# ProPrj_EPICS_Project_PCBs_2024-10-20.net
KiCad netlist of a schematic drawn in EasyEDA Pro
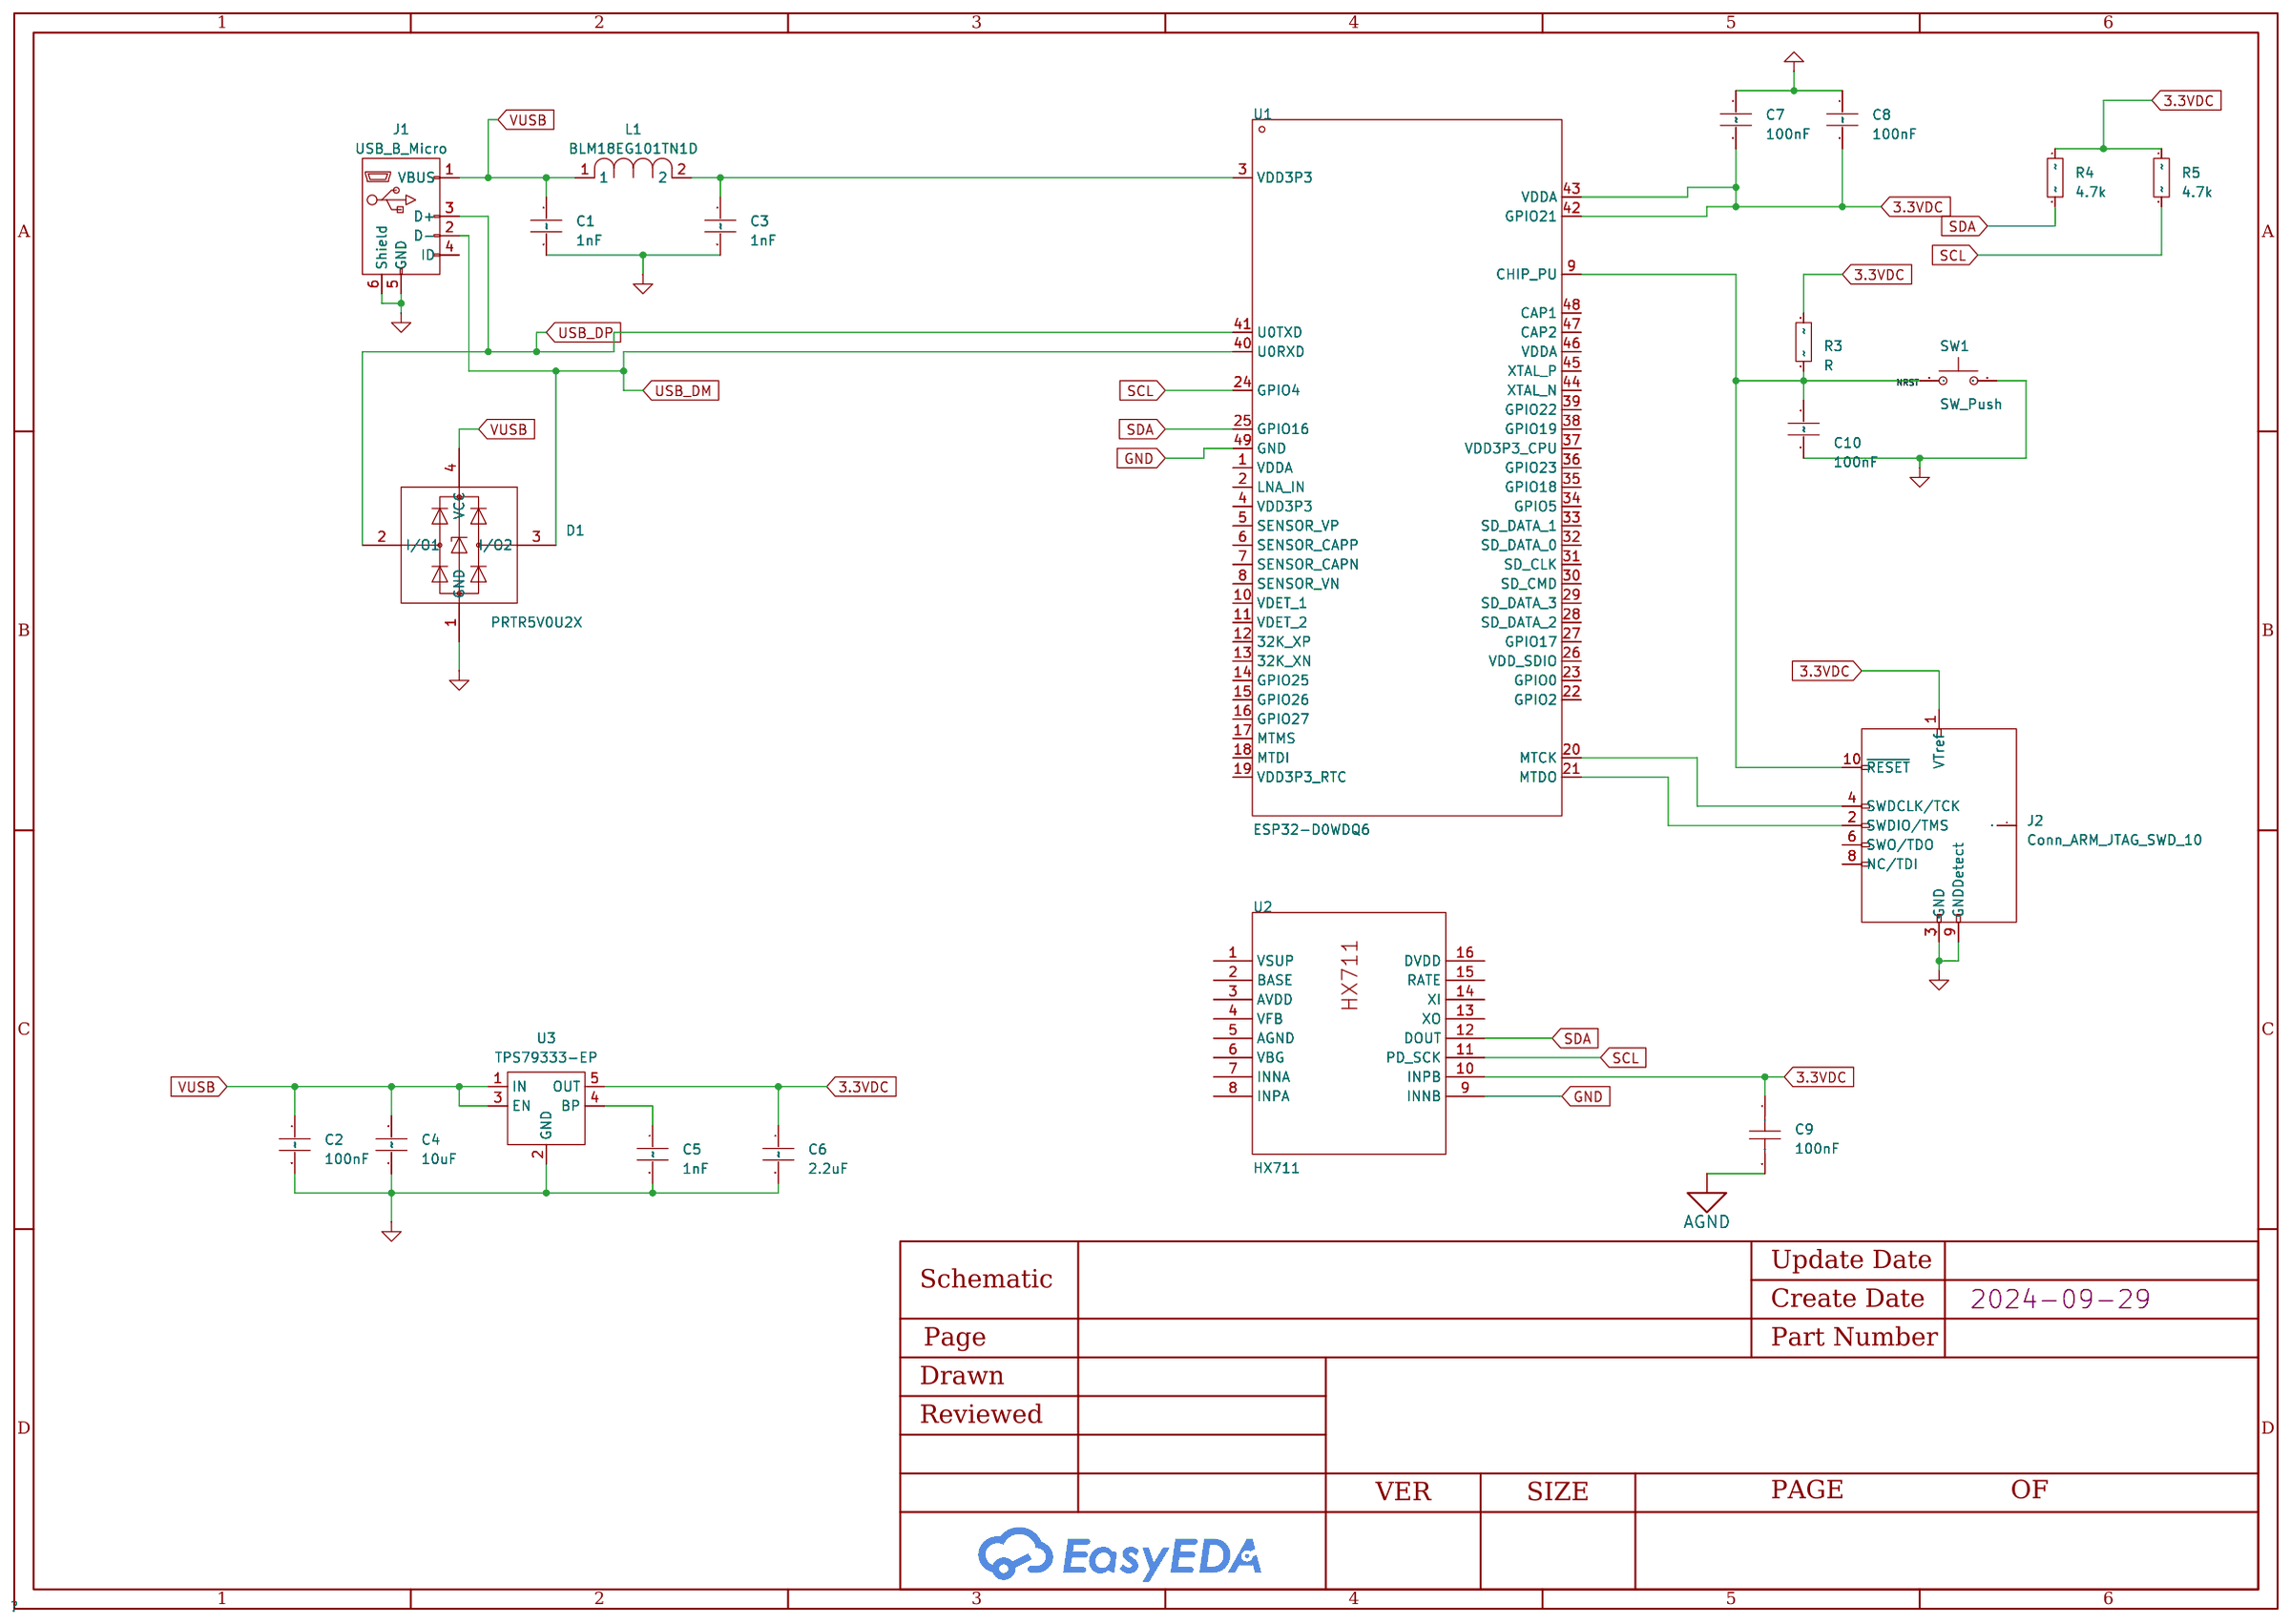
[diagram p0: schematic sheet]

(export (version "E")
  (design (tool "Eeschema 10.0.6"))
  (components
    (comp (ref "C1") (value "1nF") (libsource (lib "easyedapro") (part "Device_C")))
    (comp (ref "C2") (value "100nF") (libsource (lib "easyedapro") (part "Device_C")))
    (comp (ref "C3") (value "1nF") (libsource (lib "easyedapro") (part "Device_C")))
    (comp (ref "C4") (value "10uF") (libsource (lib "easyedapro") (part "Device_C")))
    (comp (ref "C5") (value "1nF") (libsource (lib "easyedapro") (part "Device_C")))
    (comp (ref "C6") (value "2.2uF") (libsource (lib "easyedapro") (part "Device_C")))
    (comp (ref "C7") (value "100nF") (libsource (lib "easyedapro") (part "Device_C")))
    (comp (ref "C8") (value "100nF") (libsource (lib "easyedapro") (part "Device_C")))
    (comp (ref "C9")
      (value "100nF")
      (footprint "easyedapro:C0603")
      (libsource (lib "easyedapro") (part "CAP"))
    )
    (comp (ref "C10") (value "100nF") (libsource (lib "easyedapro") (part "Device_C")))
    (comp (ref "D1") (value "PRTR5V0U2X") (libsource (lib "easyedapro") (part "Power_Protection_PRTR5V0U2X")))
    (comp (ref "J1") (value "USB_B_Micro") (libsource (lib "easyedapro") (part "Connector_USB_B_Micro")))
    (comp (ref "J2")
      (value "Conn_ARM_JTAG_SWD_10")
      (libsource (lib "easyedapro") (part "Connector_Conn_ARM_JTAG_SWD_10"))
    )
    (comp (ref "L1")
      (value "BLM18EG101TN1D")
      (libsource (lib "easyedapro") (part "COURSE_COMPONENTS_BLM18EG101TN1D"))
    )
    (comp (ref "R3") (value "R") (libsource (lib "easyedapro") (part "Device_R")))
    (comp (ref "R4") (value "4.7k") (libsource (lib "easyedapro") (part "Device_R")))
    (comp (ref "R5") (value "4.7k") (libsource (lib "easyedapro") (part "Device_R")))
    (comp (ref "SW1") (value "SW_Push") (libsource (lib "easyedapro") (part "Switch_SW_Push")))
    (comp (ref "U1")
      (value "ESP32-D0WDQ6")
      (footprint "easyedapro:QFN-48_L6.0-W6.0-P0.40-BL-EP3.8")
      (fields (field (name "Manufacturer") "ESPRESSIF(乐鑫)"))
      (libsource (lib "easyedapro") (part "ESP32-D0WDQ6"))
    )
    (comp (ref "U2")
      (value "HX711")
      (footprint "easyedapro:SOP-16_L10.0-W3.9-P1.27-LS6.0-BL")
      (fields (field (name "Manufacturer") "AVIA(海芯科技)"))
      (libsource (lib "easyedapro") (part "HX711"))
    )
    (comp (ref "U3")
      (value "TPS79333-EP")
      (libsource (lib "easyedapro") (part "Regulator_Linear_TPS79333-EP"))
    )
  )
  (nets
    (net (code "1") (name "/NRST") (class "Default")
      (node (ref "C10") (pin "2") (pinfunction "~_2") (pintype "unspecified"))
      (node (ref "J2") (pin "10") (pinfunction "~{RESET}_10") (pintype "unspecified"))
      (node (ref "R3") (pin "2") (pinfunction "~_2") (pintype "unspecified"))
      (node (ref "SW1") (pin "1") (pinfunction "1_1") (pintype "unspecified"))
      (node (ref "U1") (pin "9") (pinfunction "CHIP_PU_9") (pintype "input"))
    )
    (net (code "2") (name "3.3VDC") (class "Default")
      (node (ref "C6") (pin "1") (pinfunction "~_1") (pintype "unspecified"))
      (node (ref "C7") (pin "1") (pinfunction "~_1") (pintype "unspecified"))
      (node (ref "C8") (pin "1") (pinfunction "~_1") (pintype "unspecified"))
      (node (ref "C9") (pin "1") (pinfunction "1_1") (pintype "input"))
      (node (ref "J2") (pin "1") (pinfunction "VTref_1") (pintype "unspecified"))
      (node (ref "R3") (pin "1") (pinfunction "~_1") (pintype "unspecified"))
      (node (ref "R4") (pin "1") (pinfunction "~_1") (pintype "unspecified"))
      (node (ref "R5") (pin "1") (pinfunction "~_1") (pintype "unspecified"))
      (node (ref "U1") (pin "42") (pinfunction "GPIO21_42") (pintype "input"))
      (node (ref "U1") (pin "43") (pinfunction "VDDA_43") (pintype "input"))
      (node (ref "U2") (pin "10") (pinfunction "INPB_10") (pintype "unspecified"))
      (node (ref "U3") (pin "5") (pinfunction "OUT_5") (pintype "unspecified"))
    )
    (net (code "3") (name "AGND") (class "Default")
      (node (ref "C9") (pin "2") (pinfunction "2_2") (pintype "input"))
    )
    (net (code "4") (name "GND") (class "Default")
      (node (ref "U1") (pin "49") (pinfunction "GND_49") (pintype "input"))
      (node (ref "U2") (pin "9") (pinfunction "INNB_9") (pintype "unspecified"))
    )
    (net (code "5") (name "Net-(C3-~-Pad1)") (class "Default")
      (node (ref "C3") (pin "1") (pinfunction "~_1") (pintype "unspecified"))
      (node (ref "L1") (pin "2") (pinfunction "2_2") (pintype "unspecified"))
      (node (ref "U1") (pin "3") (pinfunction "VDD3P3_3") (pintype "input"))
    )
    (net (code "6") (name "Net-(J2-SWDCLK{slash}TCK)") (class "Default")
      (node (ref "J2") (pin "4") (pinfunction "SWDCLK/TCK_4") (pintype "output"))
      (node (ref "U1") (pin "20") (pinfunction "MTCK_20") (pintype "input"))
    )
    (net (code "7") (name "Net-(J2-SWDIO{slash}TMS)") (class "Default")
      (node (ref "J2") (pin "2") (pinfunction "SWDIO/TMS_2") (pintype "bidirectional"))
      (node (ref "U1") (pin "21") (pinfunction "MTDO_21") (pintype "input"))
    )
    (net (code "8") (name "Net-(U3-BP)") (class "Default")
      (node (ref "C5") (pin "1") (pinfunction "~_1") (pintype "unspecified"))
      (node (ref "U3") (pin "4") (pinfunction "BP_4") (pintype "bidirectional"))
    )
    (net (code "9") (name "POWER_GND") (class "Default")
      (node (ref "C1") (pin "2") (pinfunction "~_2") (pintype "unspecified"))
      (node (ref "C10") (pin "1") (pinfunction "~_1") (pintype "unspecified"))
      (node (ref "C2") (pin "2") (pinfunction "~_2") (pintype "unspecified"))
      (node (ref "C3") (pin "2") (pinfunction "~_2") (pintype "unspecified"))
      (node (ref "C4") (pin "2") (pinfunction "~_2") (pintype "unspecified"))
      (node (ref "C5") (pin "2") (pinfunction "~_2") (pintype "unspecified"))
      (node (ref "C6") (pin "2") (pinfunction "~_2") (pintype "unspecified"))
      (node (ref "C7") (pin "2") (pinfunction "~_2") (pintype "unspecified"))
      (node (ref "C8") (pin "2") (pinfunction "~_2") (pintype "unspecified"))
      (node (ref "D1") (pin "1") (pinfunction "GND_1") (pintype "unspecified"))
      (node (ref "J1") (pin "5") (pinfunction "GND_5") (pintype "unspecified"))
      (node (ref "J1") (pin "6") (pinfunction "Shield_6") (pintype "unspecified"))
      (node (ref "J2") (pin "3") (pinfunction "GND_3") (pintype "unspecified"))
      (node (ref "J2") (pin "5") (pinfunction "GND_5") (pintype "unspecified"))
      (node (ref "J2") (pin "9") (pinfunction "GNDDetect_9") (pintype "unspecified"))
      (node (ref "SW1") (pin "2") (pinfunction "2_2") (pintype "unspecified"))
      (node (ref "U3") (pin "2") (pinfunction "GND_2") (pintype "unspecified"))
    )
    (net (code "10") (name "SCL") (class "Default")
      (node (ref "R5") (pin "2") (pinfunction "~_2") (pintype "unspecified"))
      (node (ref "U1") (pin "24") (pinfunction "GPIO4_24") (pintype "input"))
      (node (ref "U2") (pin "11") (pinfunction "PD_SCK_11") (pintype "unspecified"))
    )
    (net (code "11") (name "SDA") (class "Default")
      (node (ref "R4") (pin "2") (pinfunction "~_2") (pintype "unspecified"))
      (node (ref "U1") (pin "25") (pinfunction "GPIO16_25") (pintype "input"))
      (node (ref "U2") (pin "12") (pinfunction "DOUT_12") (pintype "unspecified"))
    )
    (net (code "12") (name "USB_DM") (class "Default")
      (node (ref "D1") (pin "3") (pinfunction "I/O2_3") (pintype "unspecified"))
      (node (ref "J1") (pin "2") (pinfunction "D-_2") (pintype "bidirectional"))
      (node (ref "U1") (pin "40") (pinfunction "U0RXD_40") (pintype "input"))
    )
    (net (code "13") (name "USB_DP") (class "Default")
      (node (ref "D1") (pin "2") (pinfunction "I/O1_2") (pintype "unspecified"))
      (node (ref "J1") (pin "3") (pinfunction "D+_3") (pintype "bidirectional"))
      (node (ref "U1") (pin "41") (pinfunction "U0TXD_41") (pintype "input"))
    )
    (net (code "14") (name "VUSB") (class "Default")
      (node (ref "C1") (pin "1") (pinfunction "~_1") (pintype "unspecified"))
      (node (ref "C2") (pin "1") (pinfunction "~_1") (pintype "unspecified"))
      (node (ref "C4") (pin "1") (pinfunction "~_1") (pintype "unspecified"))
      (node (ref "D1") (pin "4") (pinfunction "VCC_4") (pintype "unspecified"))
      (node (ref "J1") (pin "1") (pinfunction "VBUS_1") (pintype "unspecified"))
      (node (ref "L1") (pin "1") (pinfunction "1_1") (pintype "unspecified"))
      (node (ref "U3") (pin "1") (pinfunction "IN_1") (pintype "unspecified"))
      (node (ref "U3") (pin "3") (pinfunction "EN_3") (pintype "input"))
    )
    (net (code "15") (name "unconnected-(J1-ID-Pad4)") (class "Default")
      (node (ref "J1") (pin "4") (pinfunction "ID_4") (pintype "unspecified"))
    )
    (net (code "16") (name "unconnected-(J2-KEY-Pad7)") (class "Default")
      (node (ref "J2") (pin "7") (pinfunction "KEY_7") (pintype "unspecified"))
    )
    (net (code "17") (name "unconnected-(J2-NC{slash}TDI-Pad8)") (class "Default")
      (node (ref "J2") (pin "8") (pinfunction "NC/TDI_8") (pintype "output"))
    )
    (net (code "18") (name "unconnected-(J2-SWO{slash}TDO-Pad6)") (class "Default")
      (node (ref "J2") (pin "6") (pinfunction "SWO/TDO_6") (pintype "input"))
    )
    (net (code "19") (name "unconnected-(U1-32K_XN-Pad13)") (class "Default")
      (node (ref "U1") (pin "13") (pinfunction "32K_XN_13") (pintype "input"))
    )
    (net (code "20") (name "unconnected-(U1-32K_XP-Pad12)") (class "Default")
      (node (ref "U1") (pin "12") (pinfunction "32K_XP_12") (pintype "input"))
    )
    (net (code "21") (name "unconnected-(U1-CAP1-Pad48)") (class "Default")
      (node (ref "U1") (pin "48") (pinfunction "CAP1_48") (pintype "input"))
    )
    (net (code "22") (name "unconnected-(U1-CAP2-Pad47)") (class "Default")
      (node (ref "U1") (pin "47") (pinfunction "CAP2_47") (pintype "input"))
    )
    (net (code "23") (name "unconnected-(U1-GPIO0-Pad23)") (class "Default")
      (node (ref "U1") (pin "23") (pinfunction "GPIO0_23") (pintype "input"))
    )
    (net (code "24") (name "unconnected-(U1-GPIO2-Pad22)") (class "Default")
      (node (ref "U1") (pin "22") (pinfunction "GPIO2_22") (pintype "input"))
    )
    (net (code "25") (name "unconnected-(U1-GPIO5-Pad34)") (class "Default")
      (node (ref "U1") (pin "34") (pinfunction "GPIO5_34") (pintype "input"))
    )
    (net (code "26") (name "unconnected-(U1-GPIO17-Pad27)") (class "Default")
      (node (ref "U1") (pin "27") (pinfunction "GPIO17_27") (pintype "input"))
    )
    (net (code "27") (name "unconnected-(U1-GPIO18-Pad35)") (class "Default")
      (node (ref "U1") (pin "35") (pinfunction "GPIO18_35") (pintype "input"))
    )
    (net (code "28") (name "unconnected-(U1-GPIO19-Pad38)") (class "Default")
      (node (ref "U1") (pin "38") (pinfunction "GPIO19_38") (pintype "input"))
    )
    (net (code "29") (name "unconnected-(U1-GPIO22-Pad39)") (class "Default")
      (node (ref "U1") (pin "39") (pinfunction "GPIO22_39") (pintype "input"))
    )
    (net (code "30") (name "unconnected-(U1-GPIO23-Pad36)") (class "Default")
      (node (ref "U1") (pin "36") (pinfunction "GPIO23_36") (pintype "input"))
    )
    (net (code "31") (name "unconnected-(U1-GPIO25-Pad14)") (class "Default")
      (node (ref "U1") (pin "14") (pinfunction "GPIO25_14") (pintype "input"))
    )
    (net (code "32") (name "unconnected-(U1-GPIO26-Pad15)") (class "Default")
      (node (ref "U1") (pin "15") (pinfunction "GPIO26_15") (pintype "input"))
    )
    (net (code "33") (name "unconnected-(U1-GPIO27-Pad16)") (class "Default")
      (node (ref "U1") (pin "16") (pinfunction "GPIO27_16") (pintype "input"))
    )
    (net (code "34") (name "unconnected-(U1-LNA_IN-Pad2)") (class "Default")
      (node (ref "U1") (pin "2") (pinfunction "LNA_IN_2") (pintype "input"))
    )
    (net (code "35") (name "unconnected-(U1-MTDI-Pad18)") (class "Default")
      (node (ref "U1") (pin "18") (pinfunction "MTDI_18") (pintype "input"))
    )
    (net (code "36") (name "unconnected-(U1-MTMS-Pad17)") (class "Default")
      (node (ref "U1") (pin "17") (pinfunction "MTMS_17") (pintype "input"))
    )
    (net (code "37") (name "unconnected-(U1-SD_CLK-Pad31)") (class "Default")
      (node (ref "U1") (pin "31") (pinfunction "SD_CLK_31") (pintype "input"))
    )
    (net (code "38") (name "unconnected-(U1-SD_CMD-Pad30)") (class "Default")
      (node (ref "U1") (pin "30") (pinfunction "SD_CMD_30") (pintype "input"))
    )
    (net (code "39") (name "unconnected-(U1-SD_DATA_0-Pad32)") (class "Default")
      (node (ref "U1") (pin "32") (pinfunction "SD_DATA_0_32") (pintype "input"))
    )
    (net (code "40") (name "unconnected-(U1-SD_DATA_1-Pad33)") (class "Default")
      (node (ref "U1") (pin "33") (pinfunction "SD_DATA_1_33") (pintype "input"))
    )
    (net (code "41") (name "unconnected-(U1-SD_DATA_2-Pad28)") (class "Default")
      (node (ref "U1") (pin "28") (pinfunction "SD_DATA_2_28") (pintype "input"))
    )
    (net (code "42") (name "unconnected-(U1-SD_DATA_3-Pad29)") (class "Default")
      (node (ref "U1") (pin "29") (pinfunction "SD_DATA_3_29") (pintype "input"))
    )
    (net (code "43") (name "unconnected-(U1-SENSOR_CAPN-Pad7)") (class "Default")
      (node (ref "U1") (pin "7") (pinfunction "SENSOR_CAPN_7") (pintype "input"))
    )
    (net (code "44") (name "unconnected-(U1-SENSOR_CAPP-Pad6)") (class "Default")
      (node (ref "U1") (pin "6") (pinfunction "SENSOR_CAPP_6") (pintype "input"))
    )
    (net (code "45") (name "unconnected-(U1-SENSOR_VN-Pad8)") (class "Default")
      (node (ref "U1") (pin "8") (pinfunction "SENSOR_VN_8") (pintype "input"))
    )
    (net (code "46") (name "unconnected-(U1-SENSOR_VP-Pad5)") (class "Default")
      (node (ref "U1") (pin "5") (pinfunction "SENSOR_VP_5") (pintype "input"))
    )
    (net (code "47") (name "unconnected-(U1-VDD3P3-Pad4)") (class "Default")
      (node (ref "U1") (pin "4") (pinfunction "VDD3P3_4") (pintype "input"))
    )
    (net (code "48") (name "unconnected-(U1-VDD3P3_CPU-Pad37)") (class "Default")
      (node (ref "U1") (pin "37") (pinfunction "VDD3P3_CPU_37") (pintype "input"))
    )
    (net (code "49") (name "unconnected-(U1-VDD3P3_RTC-Pad19)") (class "Default")
      (node (ref "U1") (pin "19") (pinfunction "VDD3P3_RTC_19") (pintype "input"))
    )
    (net (code "50") (name "unconnected-(U1-VDDA-Pad1)") (class "Default")
      (node (ref "U1") (pin "1") (pinfunction "VDDA_1") (pintype "input"))
    )
    (net (code "51") (name "unconnected-(U1-VDDA-Pad46)") (class "Default")
      (node (ref "U1") (pin "46") (pinfunction "VDDA_46") (pintype "input"))
    )
    (net (code "52") (name "unconnected-(U1-VDD_SDIO-Pad26)") (class "Default")
      (node (ref "U1") (pin "26") (pinfunction "VDD_SDIO_26") (pintype "input"))
    )
    (net (code "53") (name "unconnected-(U1-VDET_1-Pad10)") (class "Default")
      (node (ref "U1") (pin "10") (pinfunction "VDET_1_10") (pintype "input"))
    )
    (net (code "54") (name "unconnected-(U1-VDET_2-Pad11)") (class "Default")
      (node (ref "U1") (pin "11") (pinfunction "VDET_2_11") (pintype "input"))
    )
    (net (code "55") (name "unconnected-(U1-XTAL_N-Pad44)") (class "Default")
      (node (ref "U1") (pin "44") (pinfunction "XTAL_N_44") (pintype "input"))
    )
    (net (code "56") (name "unconnected-(U1-XTAL_P-Pad45)") (class "Default")
      (node (ref "U1") (pin "45") (pinfunction "XTAL_P_45") (pintype "input"))
    )
    (net (code "57") (name "unconnected-(U2-AGND-Pad5)") (class "Default")
      (node (ref "U2") (pin "5") (pinfunction "AGND_5") (pintype "unspecified"))
    )
    (net (code "58") (name "unconnected-(U2-AVDD-Pad3)") (class "Default")
      (node (ref "U2") (pin "3") (pinfunction "AVDD_3") (pintype "unspecified"))
    )
    (net (code "59") (name "unconnected-(U2-BASE-Pad2)") (class "Default")
      (node (ref "U2") (pin "2") (pinfunction "BASE_2") (pintype "unspecified"))
    )
    (net (code "60") (name "unconnected-(U2-DVDD-Pad16)") (class "Default")
      (node (ref "U2") (pin "16") (pinfunction "DVDD_16") (pintype "unspecified"))
    )
    (net (code "61") (name "unconnected-(U2-INNA-Pad7)") (class "Default")
      (node (ref "U2") (pin "7") (pinfunction "INNA_7") (pintype "unspecified"))
    )
    (net (code "62") (name "unconnected-(U2-INPA-Pad8)") (class "Default")
      (node (ref "U2") (pin "8") (pinfunction "INPA_8") (pintype "unspecified"))
    )
    (net (code "63") (name "unconnected-(U2-RATE-Pad15)") (class "Default")
      (node (ref "U2") (pin "15") (pinfunction "RATE_15") (pintype "unspecified"))
    )
    (net (code "64") (name "unconnected-(U2-VBG-Pad6)") (class "Default")
      (node (ref "U2") (pin "6") (pinfunction "VBG_6") (pintype "unspecified"))
    )
    (net (code "65") (name "unconnected-(U2-VFB-Pad4)") (class "Default")
      (node (ref "U2") (pin "4") (pinfunction "VFB_4") (pintype "unspecified"))
    )
    (net (code "66") (name "unconnected-(U2-VSUP-Pad1)") (class "Default")
      (node (ref "U2") (pin "1") (pinfunction "VSUP_1") (pintype "unspecified"))
    )
    (net (code "67") (name "unconnected-(U2-XI-Pad14)") (class "Default")
      (node (ref "U2") (pin "14") (pinfunction "XI_14") (pintype "unspecified"))
    )
    (net (code "68") (name "unconnected-(U2-XO-Pad13)") (class "Default")
      (node (ref "U2") (pin "13") (pinfunction "XO_13") (pintype "unspecified"))
    )
  )
)
